# au6850_mp3.net
KiCad netlist of a schematic drawn in EAGLE
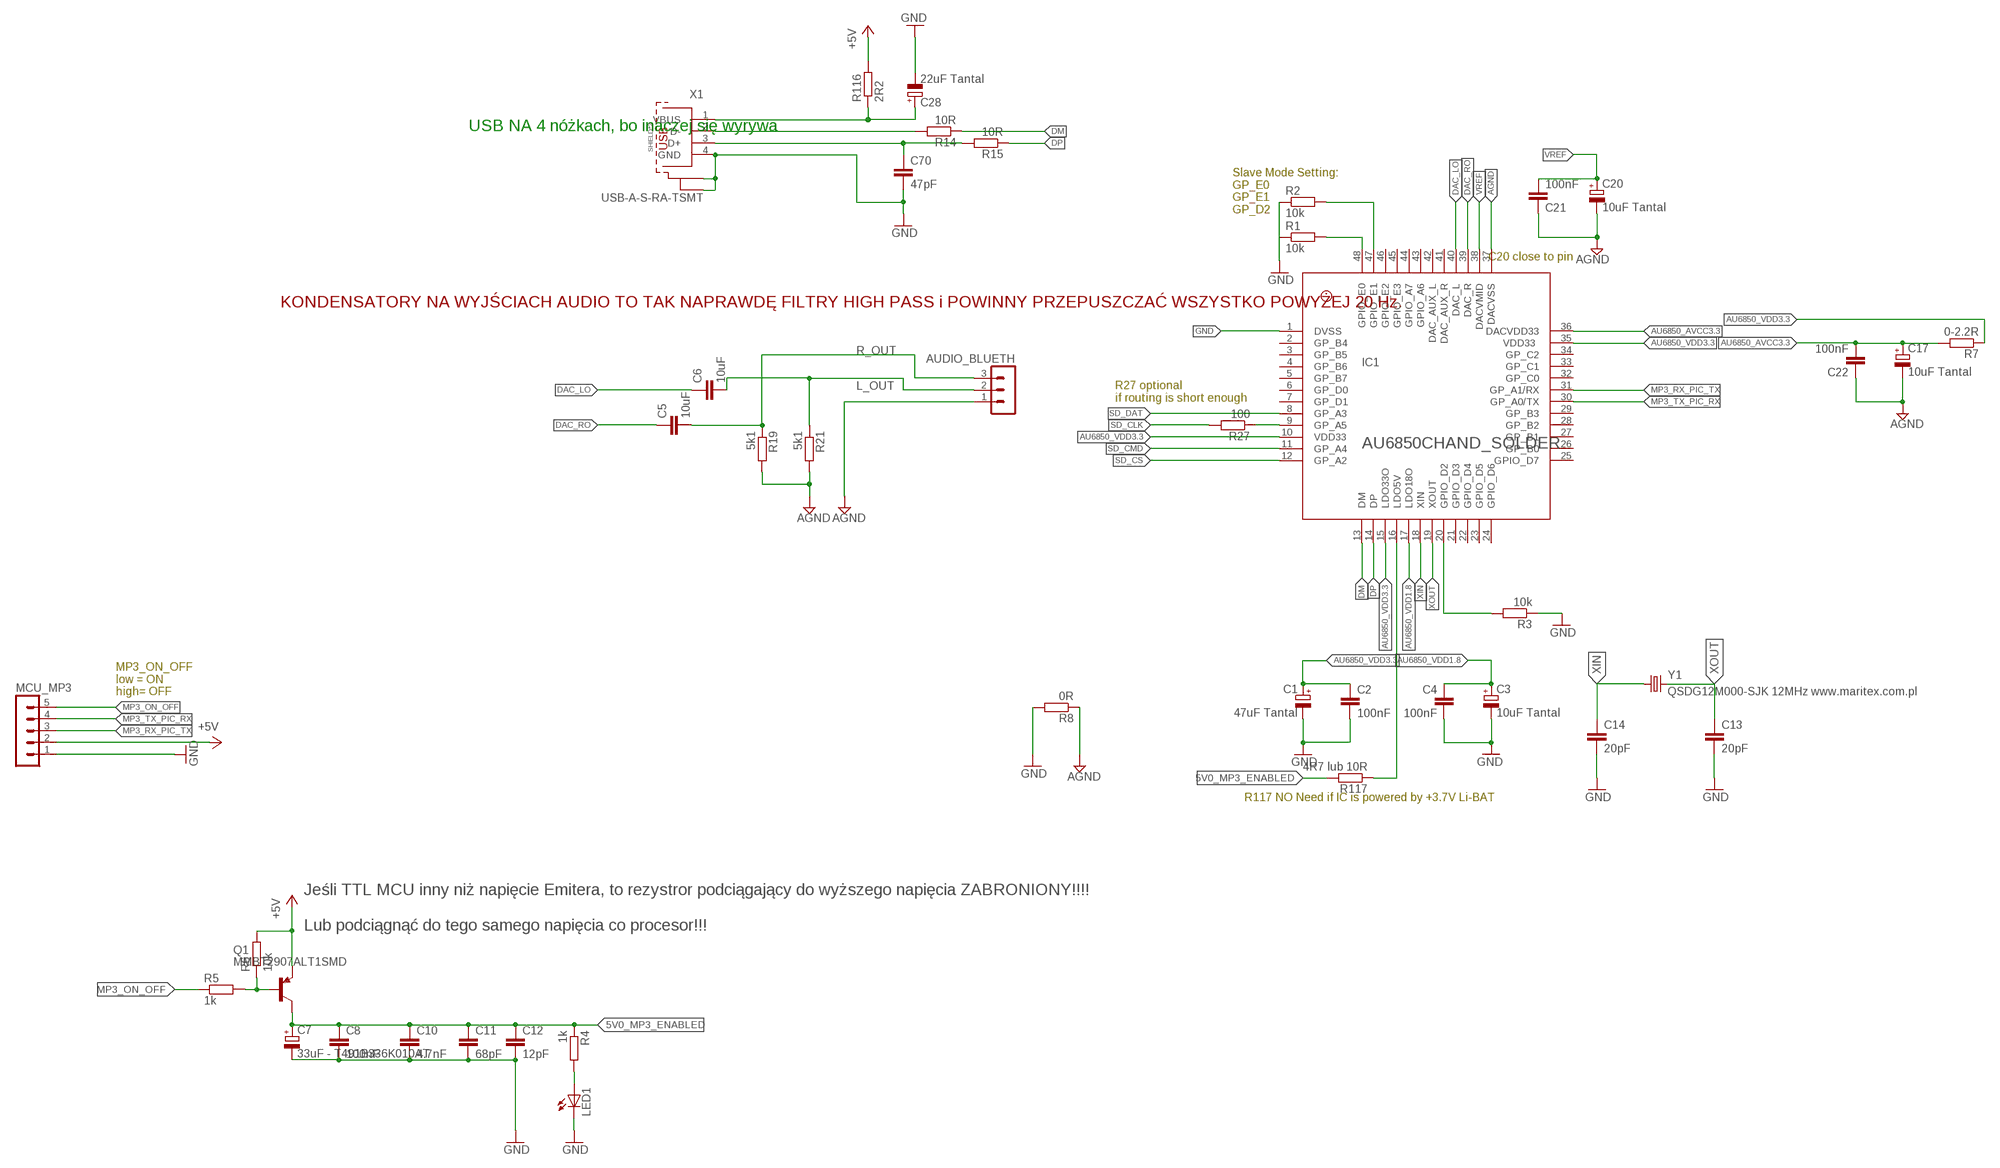
[diagram p0: schematic, sheet 1, part 1 of 2]
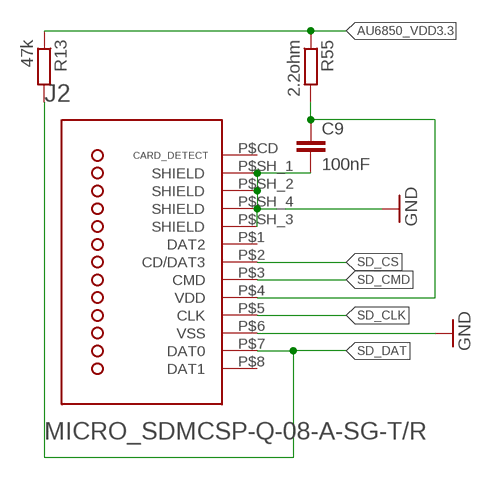
[diagram p1: schematic, sheet 1, part 2 of 2]

(export (version "E")
  (design (tool "Eeschema 10.0.6"))
  (components
    (comp (ref "AUDIO_BLUETH")
      (value "MA03-1")
      (footprint "eagle-import:MA03-1")
      (libsource (lib "eagle-import") (part "MA03-1"))
    )
    (comp (ref "C1")
      (value "47uF Tantal")
      (footprint "eagle-import:B_3528-21R")
      (fields (field (name "PARTNUM") "TAJB476K010R") (field (name "SUPPLIER") "TME"))
      (libsource (lib "eagle-import") (part "CPOL-EUB/3528-21R"))
    )
    (comp (ref "C2")
      (value "100nF")
      (footprint "eagle-import:C0805")
      (libsource (lib "eagle-import") (part "C-EUC0805"))
    )
    (comp (ref "C3")
      (value "10uF Tantal")
      (footprint "eagle-import:B_3528-21R")
      (fields (field (name "PARTNUM") "TAJA106K010R") (field (name "SUPPLIER") "TME"))
      (libsource (lib "eagle-import") (part "CPOL-EUB/3528-21R"))
    )
    (comp (ref "C4")
      (value "100nF")
      (footprint "eagle-import:C0805")
      (libsource (lib "eagle-import") (part "C-EUC0805"))
    )
    (comp (ref "C5")
      (value "10uF")
      (footprint "eagle-import:C0805")
      (libsource (lib "eagle-import") (part "C-EUC0805"))
    )
    (comp (ref "C6")
      (value "10uF")
      (footprint "eagle-import:C0805")
      (libsource (lib "eagle-import") (part "C-EUC0805"))
    )
    (comp (ref "C7")
      (value "33uF - T491B336K010AT")
      (footprint "eagle-import:SMC_B")
      (fields (field (name "PARTNUM") "TAJB336K010R") (field (name "SUPPLIER") "TME"))
      (libsource (lib "eagle-import") (part "resistor_CPOL-EUSMCB"))
    )
    (comp (ref "C8")
      (value "100nF")
      (footprint "eagle-import:C0805")
      (libsource (lib "eagle-import") (part "resistor_C-EUC0805"))
    )
    (comp (ref "C9")
      (value "100nF")
      (footprint "eagle-import:C0805")
      (libsource (lib "eagle-import") (part "resistor_C-EUC0805"))
    )
    (comp (ref "C10")
      (value "4.7nF")
      (footprint "eagle-import:C0805")
      (libsource (lib "eagle-import") (part "resistor_C-EUC0805"))
    )
    (comp (ref "C11")
      (value "68pF")
      (footprint "eagle-import:C0805")
      (libsource (lib "eagle-import") (part "resistor_C-EUC0805"))
    )
    (comp (ref "C12")
      (value "12pF")
      (footprint "eagle-import:C0603K")
      (libsource (lib "eagle-import") (part "resistor_C-EUC0603K"))
    )
    (comp (ref "C13")
      (value "20pF")
      (footprint "eagle-import:C0805")
      (libsource (lib "eagle-import") (part "resistor_C-EUC0805"))
    )
    (comp (ref "C14")
      (value "20pF")
      (footprint "eagle-import:C0805")
      (libsource (lib "eagle-import") (part "resistor_C-EUC0805"))
    )
    (comp (ref "C17")
      (value "10uF Tantal")
      (footprint "eagle-import:B_3528-21R")
      (libsource (lib "eagle-import") (part "CPOL-EUB/3528-21R"))
    )
    (comp (ref "C20")
      (value "10uF Tantal")
      (footprint "eagle-import:B_3528-21R")
      (libsource (lib "eagle-import") (part "CPOL-EUB/3528-21R"))
    )
    (comp (ref "C21")
      (value "100nF")
      (footprint "eagle-import:C0805")
      (libsource (lib "eagle-import") (part "C-EUC0805"))
    )
    (comp (ref "C22")
      (value "100nF")
      (footprint "eagle-import:C0805")
      (libsource (lib "eagle-import") (part "C-EUC0805"))
    )
    (comp (ref "C28")
      (value "22uF Tantal")
      (footprint "eagle-import:SMC_B")
      (fields (field (name "PARTNUM") "TAJB226M010R"))
      (libsource (lib "eagle-import") (part "CPOL-EUSMCB"))
    )
    (comp (ref "C70")
      (value "47pF")
      (footprint "eagle-import:C0805")
      (libsource (lib "eagle-import") (part "resistor_C-EUC0805"))
    )
    (comp (ref "IC1")
      (value "AU6850CHAND_SOLDER")
      (footprint "eagle-import:LQFP48-7X7_3MM")
      (libsource (lib "eagle-import") (part "AU6850CHAND_SOLDER"))
    )
    (comp (ref "J2")
      (value "MICRO_SDMCSP-Q-08-A-SG-T/R")
      (footprint "eagle-import:MICRO_SD_8PINS")
      (fields (field (name "PARTNUM") "MCSP-Q-08-A-SG-T/R"))
      (libsource (lib "eagle-import") (part "MICRO_SDMCSP-Q-08-A-SG-T/R"))
    )
    (comp (ref "LED1")
      (value "LED3MM")
      (footprint "eagle-import:LED3MM")
      (libsource (lib "eagle-import") (part "LED3MM"))
    )
    (comp (ref "MCU_MP3")
      (value "MA05-1")
      (footprint "eagle-import:MA05-1")
      (libsource (lib "eagle-import") (part "MA05-1"))
    )
    (comp (ref "Q1")
      (value "MMBT2907ALT1SMD")
      (footprint "eagle-import:SOT23-BEC")
      (libsource (lib "eagle-import") (part "MMBT2907SMDALT1"))
    )
    (comp (ref "R1")
      (value "10k")
      (footprint "eagle-import:R0805")
      (libsource (lib "eagle-import") (part "R-EU_R0805"))
    )
    (comp (ref "R2")
      (value "10k")
      (footprint "eagle-import:R0805")
      (libsource (lib "eagle-import") (part "R-EU_R0805"))
    )
    (comp (ref "R3")
      (value "10k")
      (footprint "eagle-import:R0805")
      (libsource (lib "eagle-import") (part "R-EU_R0805"))
    )
    (comp (ref "R4")
      (value "1k")
      (footprint "eagle-import:M0805")
      (libsource (lib "eagle-import") (part "R-EU_M0805"))
    )
    (comp (ref "R5")
      (value "1k")
      (footprint "eagle-import:M0805")
      (libsource (lib "eagle-import") (part "R-EU_M0805"))
    )
    (comp (ref "R6")
      (value "10k")
      (footprint "eagle-import:M0805")
      (libsource (lib "eagle-import") (part "R-EU_M0805"))
    )
    (comp (ref "R7")
      (value "0-2.2R")
      (footprint "eagle-import:R0805")
      (libsource (lib "eagle-import") (part "R-EU_R0805"))
    )
    (comp (ref "R8")
      (value "0R")
      (footprint "eagle-import:R0805")
      (libsource (lib "eagle-import") (part "R-EU_R0805"))
    )
    (comp (ref "R13")
      (value "47k")
      (footprint "eagle-import:R0805")
      (libsource (lib "eagle-import") (part "R-EU_R0805"))
    )
    (comp (ref "R14")
      (value "10R")
      (footprint "eagle-import:R0805")
      (libsource (lib "eagle-import") (part "R-EU_R0805"))
    )
    (comp (ref "R15")
      (value "10R")
      (footprint "eagle-import:R0805")
      (libsource (lib "eagle-import") (part "R-EU_R0805"))
    )
    (comp (ref "R19")
      (value "5k1")
      (footprint "eagle-import:R0805")
      (libsource (lib "eagle-import") (part "R-EU_R0805"))
    )
    (comp (ref "R21")
      (value "5k1")
      (footprint "eagle-import:R0805")
      (libsource (lib "eagle-import") (part "R-EU_R0805"))
    )
    (comp (ref "R27")
      (value "100")
      (footprint "eagle-import:R0805")
      (libsource (lib "eagle-import") (part "R-EU_R0805"))
    )
    (comp (ref "R55")
      (value "2.2ohm")
      (footprint "eagle-import:R0805")
      (libsource (lib "eagle-import") (part "R-EU_R0805"))
    )
    (comp (ref "R116")
      (value "2R2")
      (footprint "eagle-import:R0805")
      (libsource (lib "eagle-import") (part "R-EU_R0805"))
    )
    (comp (ref "R117")
      (value "4R7 lub 10R")
      (footprint "eagle-import:R0805")
      (libsource (lib "eagle-import") (part "R-EU_R0805"))
    )
    (comp (ref "X1")
      (value "USB-A-S-RA-TSMT")
      (footprint "eagle-import:USB-A-S-RA-TSMT")
      (libsource (lib "eagle-import") (part "USB-A-S-RA-TSMT"))
    )
    (comp (ref "Y1")
      (value "QSDG12M000-SJK 12MHz www.maritex.com.pl")
      (footprint "eagle-import:HC49UP")
      (fields (field (name "PARTNUM") "12.00M-SMDHC49S"))
      (libsource (lib "eagle-import") (part "CRYSTALSMD"))
    )
  )
  (nets
    (net (code "1") (name "+5V") (class "Default")
      (node (ref "MCU_MP3") (pin "2") (pinfunction "2_2") (pintype "passive"))
      (node (ref "Q1") (pin "E") (pinfunction "E_E") (pintype "passive"))
      (node (ref "R116") (pin "2") (pinfunction "2_2") (pintype "passive"))
      (node (ref "R6") (pin "2") (pinfunction "2_2") (pintype "passive"))
    )
    (net (code "2") (name "/L_OUT") (class "Default")
      (node (ref "AUDIO_BLUETH") (pin "2") (pinfunction "2_2") (pintype "passive"))
      (node (ref "C6") (pin "2") (pinfunction "2_2") (pintype "passive"))
      (node (ref "R21") (pin "1") (pinfunction "1_1") (pintype "passive"))
    )
    (net (code "3") (name "/R_OUT") (class "Default")
      (node (ref "AUDIO_BLUETH") (pin "3") (pinfunction "3_3") (pintype "passive"))
      (node (ref "C5") (pin "2") (pinfunction "2_2") (pintype "passive"))
      (node (ref "R19") (pin "1") (pinfunction "1_1") (pintype "passive"))
    )
    (net (code "4") (name "5V0_MP3_ENABLED") (class "Default")
      (node (ref "C10") (pin "1") (pinfunction "1_1") (pintype "passive"))
      (node (ref "C11") (pin "1") (pinfunction "1_1") (pintype "passive"))
      (node (ref "C12") (pin "1") (pinfunction "1_1") (pintype "passive"))
      (node (ref "C7") (pin "+") (pinfunction "+_+") (pintype "passive"))
      (node (ref "C8") (pin "1") (pinfunction "1_1") (pintype "passive"))
      (node (ref "Q1") (pin "C") (pinfunction "C_C") (pintype "passive"))
      (node (ref "R117") (pin "2") (pinfunction "2_2") (pintype "passive"))
      (node (ref "R4") (pin "1") (pinfunction "1_1") (pintype "passive"))
    )
    (net (code "5") (name "AGND") (class "Default")
      (node (ref "AUDIO_BLUETH") (pin "1") (pinfunction "1_1") (pintype "passive"))
      (node (ref "C17") (pin "-") (pinfunction "-_-") (pintype "passive"))
      (node (ref "C20") (pin "-") (pinfunction "-_-") (pintype "passive"))
      (node (ref "C21") (pin "1") (pinfunction "1_1") (pintype "passive"))
      (node (ref "C22") (pin "1") (pinfunction "1_1") (pintype "passive"))
      (node (ref "IC1") (pin "37") (pinfunction "DACVSS_37") (pintype "input"))
      (node (ref "R19") (pin "2") (pinfunction "2_2") (pintype "passive"))
      (node (ref "R21") (pin "2") (pinfunction "2_2") (pintype "passive"))
      (node (ref "R8") (pin "1") (pinfunction "1_1") (pintype "passive"))
    )
    (net (code "6") (name "AU6850_AVCC3.3") (class "Default")
      (node (ref "C17") (pin "+") (pinfunction "+_+") (pintype "passive"))
      (node (ref "C22") (pin "2") (pinfunction "2_2") (pintype "passive"))
      (node (ref "IC1") (pin "36") (pinfunction "DACVDD33_36") (pintype "input"))
      (node (ref "R7") (pin "2") (pinfunction "2_2") (pintype "passive"))
    )
    (net (code "7") (name "AU6850_VDD1.8") (class "Default")
      (node (ref "C3") (pin "+") (pinfunction "+_+") (pintype "passive"))
      (node (ref "C4") (pin "1") (pinfunction "1_1") (pintype "passive"))
      (node (ref "IC1") (pin "17") (pinfunction "LDO18O_17") (pintype "bidirectional"))
    )
    (net (code "8") (name "AU6850_VDD3.3") (class "Default")
      (node (ref "C1") (pin "+") (pinfunction "+_+") (pintype "passive"))
      (node (ref "C2") (pin "1") (pinfunction "1_1") (pintype "passive"))
      (node (ref "IC1") (pin "10") (pinfunction "VDD33_10") (pintype "power_in"))
      (node (ref "IC1") (pin "15") (pinfunction "LDO33O_15") (pintype "output"))
      (node (ref "IC1") (pin "35") (pinfunction "VDD33_35") (pintype "input"))
      (node (ref "R13") (pin "1") (pinfunction "1_1") (pintype "passive"))
      (node (ref "R55") (pin "1") (pinfunction "1_1") (pintype "passive"))
      (node (ref "R7") (pin "1") (pinfunction "1_1") (pintype "passive"))
    )
    (net (code "9") (name "DAC_LO") (class "Default")
      (node (ref "C6") (pin "1") (pinfunction "1_1") (pintype "passive"))
      (node (ref "IC1") (pin "40") (pinfunction "DAC_L_40") (pintype "output"))
    )
    (net (code "10") (name "DAC_RO") (class "Default")
      (node (ref "C5") (pin "1") (pinfunction "1_1") (pintype "passive"))
      (node (ref "IC1") (pin "39") (pinfunction "DAC_R_39") (pintype "output"))
    )
    (net (code "11") (name "DM") (class "Default")
      (node (ref "IC1") (pin "13") (pinfunction "DM_13") (pintype "bidirectional"))
      (node (ref "R14") (pin "1") (pinfunction "1_1") (pintype "passive"))
    )
    (net (code "12") (name "DP") (class "Default")
      (node (ref "IC1") (pin "14") (pinfunction "DP_14") (pintype "bidirectional"))
      (node (ref "R15") (pin "1") (pinfunction "1_1") (pintype "passive"))
    )
    (net (code "13") (name "GND") (class "Default")
      (node (ref "C1") (pin "-") (pinfunction "-_-") (pintype "passive"))
      (node (ref "C10") (pin "2") (pinfunction "2_2") (pintype "passive"))
      (node (ref "C11") (pin "2") (pinfunction "2_2") (pintype "passive"))
      (node (ref "C12") (pin "2") (pinfunction "2_2") (pintype "passive"))
      (node (ref "C13") (pin "2") (pinfunction "2_2") (pintype "passive"))
      (node (ref "C14") (pin "2") (pinfunction "2_2") (pintype "passive"))
      (node (ref "C2") (pin "2") (pinfunction "2_2") (pintype "passive"))
      (node (ref "C28") (pin "-") (pinfunction "-_-") (pintype "passive"))
      (node (ref "C3") (pin "-") (pinfunction "-_-") (pintype "passive"))
      (node (ref "C4") (pin "2") (pinfunction "2_2") (pintype "passive"))
      (node (ref "C7") (pin "-") (pinfunction "-_-") (pintype "passive"))
      (node (ref "C70") (pin "2") (pinfunction "2_2") (pintype "passive"))
      (node (ref "C8") (pin "2") (pinfunction "2_2") (pintype "passive"))
      (node (ref "C9") (pin "2") (pinfunction "2_2") (pintype "passive"))
      (node (ref "IC1") (pin "1") (pinfunction "DVSS_1") (pintype "bidirectional"))
      (node (ref "J2") (pin "P$6") (pinfunction "VSS_P$6") (pintype "bidirectional"))
      (node (ref "J2") (pin "P$SH_1") (pinfunction "1_GND_PAD_P$SH_1") (pintype "bidirectional"))
      (node (ref "J2") (pin "P$SH_2") (pinfunction "2_GND_PAD_P$SH_2") (pintype "bidirectional"))
      (node (ref "J2") (pin "P$SH_3") (pinfunction "3_GND_PAD_P$SH_3") (pintype "bidirectional"))
      (node (ref "J2") (pin "P$SH_4") (pinfunction "4_GND_PAD_P$SH_4") (pintype "bidirectional"))
      (node (ref "LED1") (pin "K") (pinfunction "C_K") (pintype "passive"))
      (node (ref "MCU_MP3") (pin "1") (pinfunction "1_1") (pintype "passive"))
      (node (ref "R1") (pin "1") (pinfunction "1_1") (pintype "passive"))
      (node (ref "R2") (pin "1") (pinfunction "1_1") (pintype "passive"))
      (node (ref "R3") (pin "1") (pinfunction "1_1") (pintype "passive"))
      (node (ref "R8") (pin "2") (pinfunction "2_2") (pintype "passive"))
      (node (ref "X1") (pin "4") (pinfunction "GND_4") (pintype "power_in"))
      (node (ref "X1") (pin "5") (pinfunction "SH1_5") (pintype "power_in"))
      (node (ref "X1") (pin "6") (pinfunction "SH2_6") (pintype "power_in"))
    )
    (net (code "14") (name "MP3_ON_OFF") (class "Default")
      (node (ref "MCU_MP3") (pin "5") (pinfunction "5_5") (pintype "passive"))
      (node (ref "R5") (pin "1") (pinfunction "1_1") (pintype "passive"))
    )
    (net (code "15") (name "MP3_RX_PIC_TX") (class "Default")
      (node (ref "IC1") (pin "31") (pinfunction "GP_A1/RX_31") (pintype "bidirectional"))
      (node (ref "MCU_MP3") (pin "3") (pinfunction "3_3") (pintype "passive"))
    )
    (net (code "16") (name "MP3_TX_PIC_RX") (class "Default")
      (node (ref "IC1") (pin "30") (pinfunction "GP_A0/TX_30") (pintype "bidirectional"))
      (node (ref "MCU_MP3") (pin "4") (pinfunction "4_4") (pintype "passive"))
    )
    (net (code "17") (name "Net-(IC1-GPIO_D2)") (class "Default")
      (node (ref "IC1") (pin "20") (pinfunction "GPIO_D2_20") (pintype "bidirectional"))
      (node (ref "R3") (pin "2") (pinfunction "2_2") (pintype "passive"))
    )
    (net (code "18") (name "Net-(IC1-GPIO_E0)") (class "Default")
      (node (ref "IC1") (pin "48") (pinfunction "GPIO_E0_48") (pintype "bidirectional"))
      (node (ref "R1") (pin "2") (pinfunction "2_2") (pintype "passive"))
    )
    (net (code "19") (name "Net-(IC1-GPIO_E1)") (class "Default")
      (node (ref "IC1") (pin "47") (pinfunction "GPIO_E1_47") (pintype "bidirectional"))
      (node (ref "R2") (pin "2") (pinfunction "2_2") (pintype "passive"))
    )
    (net (code "20") (name "Net-(IC1-GP_A5)") (class "Default")
      (node (ref "IC1") (pin "9") (pinfunction "GP_A5_9") (pintype "bidirectional"))
      (node (ref "R27") (pin "1") (pinfunction "1_1") (pintype "passive"))
    )
    (net (code "21") (name "Net-(IC1-LDO5V)") (class "Default")
      (node (ref "IC1") (pin "16") (pinfunction "LDO5V_16") (pintype "bidirectional"))
      (node (ref "R117") (pin "1") (pinfunction "1_1") (pintype "passive"))
    )
    (net (code "22") (name "Net-(J2-VDD)") (class "Default")
      (node (ref "C9") (pin "1") (pinfunction "1_1") (pintype "passive"))
      (node (ref "J2") (pin "P$4") (pinfunction "VDD_P$4") (pintype "bidirectional"))
      (node (ref "R55") (pin "2") (pinfunction "2_2") (pintype "passive"))
    )
    (net (code "23") (name "Net-(LED1-PadA)") (class "Default")
      (node (ref "LED1") (pin "A") (pinfunction "A_A") (pintype "passive"))
      (node (ref "R4") (pin "2") (pinfunction "2_2") (pintype "passive"))
    )
    (net (code "24") (name "Net-(Q1-PadB)") (class "Default")
      (node (ref "Q1") (pin "B") (pinfunction "B_B") (pintype "passive"))
      (node (ref "R5") (pin "2") (pinfunction "2_2") (pintype "passive"))
      (node (ref "R6") (pin "1") (pinfunction "1_1") (pintype "passive"))
    )
    (net (code "25") (name "Net-(X1-D+)") (class "Default")
      (node (ref "C70") (pin "1") (pinfunction "1_1") (pintype "passive"))
      (node (ref "R15") (pin "2") (pinfunction "2_2") (pintype "passive"))
      (node (ref "X1") (pin "3") (pinfunction "D+_3") (pintype "bidirectional"))
    )
    (net (code "26") (name "Net-(X1-D-)") (class "Default")
      (node (ref "R14") (pin "2") (pinfunction "2_2") (pintype "passive"))
      (node (ref "X1") (pin "2") (pinfunction "D-_2") (pintype "bidirectional"))
    )
    (net (code "27") (name "Net-(X1-VBUS)") (class "Default")
      (node (ref "C28") (pin "+") (pinfunction "+_+") (pintype "passive"))
      (node (ref "R116") (pin "1") (pinfunction "1_1") (pintype "passive"))
      (node (ref "X1") (pin "1") (pinfunction "VBUS_1") (pintype "power_in"))
    )
    (net (code "28") (name "SD_CLK") (class "Default")
      (node (ref "J2") (pin "P$5") (pinfunction "CLK_P$5") (pintype "bidirectional"))
      (node (ref "R27") (pin "2") (pinfunction "2_2") (pintype "passive"))
    )
    (net (code "29") (name "SD_CMD") (class "Default")
      (node (ref "IC1") (pin "11") (pinfunction "GP_A4_11") (pintype "bidirectional"))
      (node (ref "J2") (pin "P$3") (pinfunction "CMD_P$3") (pintype "bidirectional"))
    )
    (net (code "30") (name "SD_CS") (class "Default")
      (node (ref "IC1") (pin "12") (pinfunction "GP_A2_12") (pintype "bidirectional"))
      (node (ref "J2") (pin "P$2") (pinfunction "CD/DAT3_P$2") (pintype "bidirectional"))
    )
    (net (code "31") (name "SD_DAT") (class "Default")
      (node (ref "IC1") (pin "8") (pinfunction "GP_A3_8") (pintype "bidirectional"))
      (node (ref "J2") (pin "P$7") (pinfunction "DAT0_P$7") (pintype "bidirectional"))
      (node (ref "R13") (pin "2") (pinfunction "2_2") (pintype "passive"))
    )
    (net (code "32") (name "VREF") (class "Default")
      (node (ref "C20") (pin "+") (pinfunction "+_+") (pintype "passive"))
      (node (ref "C21") (pin "2") (pinfunction "2_2") (pintype "passive"))
      (node (ref "IC1") (pin "38") (pinfunction "DACVMID_38") (pintype "input"))
    )
    (net (code "33") (name "XIN") (class "Default")
      (node (ref "C14") (pin "1") (pinfunction "1_1") (pintype "passive"))
      (node (ref "IC1") (pin "18") (pinfunction "XIN_18") (pintype "input"))
      (node (ref "Y1") (pin "1") (pinfunction "1_1") (pintype "passive"))
    )
    (net (code "34") (name "XOUT") (class "Default")
      (node (ref "C13") (pin "1") (pinfunction "1_1") (pintype "passive"))
      (node (ref "IC1") (pin "19") (pinfunction "XOUT_19") (pintype "output"))
      (node (ref "Y1") (pin "2") (pinfunction "2_2") (pintype "passive"))
    )
    (net (code "35") (name "unconnected-(IC1-DAC_AUX_L-Pad42)") (class "Default")
      (node (ref "IC1") (pin "42") (pinfunction "DAC_AUX_L_42") (pintype "input"))
    )
    (net (code "36") (name "unconnected-(IC1-DAC_AUX_R-Pad41)") (class "Default")
      (node (ref "IC1") (pin "41") (pinfunction "DAC_AUX_R_41") (pintype "input"))
    )
    (net (code "37") (name "unconnected-(IC1-GPIO_A6-Pad43)") (class "Default")
      (node (ref "IC1") (pin "43") (pinfunction "GPIO_A6_43") (pintype "bidirectional"))
    )
    (net (code "38") (name "unconnected-(IC1-GPIO_A7-Pad44)") (class "Default")
      (node (ref "IC1") (pin "44") (pinfunction "GPIO_A7_44") (pintype "bidirectional"))
    )
    (net (code "39") (name "unconnected-(IC1-GPIO_D3-Pad21)") (class "Default")
      (node (ref "IC1") (pin "21") (pinfunction "GPIO_D3_21") (pintype "bidirectional"))
    )
    (net (code "40") (name "unconnected-(IC1-GPIO_D4-Pad22)") (class "Default")
      (node (ref "IC1") (pin "22") (pinfunction "GPIO_D4_22") (pintype "bidirectional"))
    )
    (net (code "41") (name "unconnected-(IC1-GPIO_D5-Pad23)") (class "Default")
      (node (ref "IC1") (pin "23") (pinfunction "GPIO_D5_23") (pintype "bidirectional"))
    )
    (net (code "42") (name "unconnected-(IC1-GPIO_D6-Pad24)") (class "Default")
      (node (ref "IC1") (pin "24") (pinfunction "GPIO_D6_24") (pintype "bidirectional"))
    )
    (net (code "43") (name "unconnected-(IC1-GPIO_D7-Pad25)") (class "Default")
      (node (ref "IC1") (pin "25") (pinfunction "GPIO_D7_25") (pintype "bidirectional"))
    )
    (net (code "44") (name "unconnected-(IC1-GPIO_E2-Pad46)") (class "Default")
      (node (ref "IC1") (pin "46") (pinfunction "GPIO_E2_46") (pintype "bidirectional"))
    )
    (net (code "45") (name "unconnected-(IC1-GPIO_E3-Pad45)") (class "Default")
      (node (ref "IC1") (pin "45") (pinfunction "GPIO_E3_45") (pintype "bidirectional"))
    )
    (net (code "46") (name "unconnected-(IC1-GP_B0-Pad26)") (class "Default")
      (node (ref "IC1") (pin "26") (pinfunction "GP_B0_26") (pintype "bidirectional"))
    )
    (net (code "47") (name "unconnected-(IC1-GP_B1-Pad27)") (class "Default")
      (node (ref "IC1") (pin "27") (pinfunction "GP_B1_27") (pintype "bidirectional"))
    )
    (net (code "48") (name "unconnected-(IC1-GP_B2-Pad28)") (class "Default")
      (node (ref "IC1") (pin "28") (pinfunction "GP_B2_28") (pintype "bidirectional"))
    )
    (net (code "49") (name "unconnected-(IC1-GP_B3-Pad29)") (class "Default")
      (node (ref "IC1") (pin "29") (pinfunction "GP_B3_29") (pintype "bidirectional"))
    )
    (net (code "50") (name "unconnected-(IC1-GP_B4-Pad2)") (class "Default")
      (node (ref "IC1") (pin "2") (pinfunction "GP_B4_2") (pintype "bidirectional"))
    )
    (net (code "51") (name "unconnected-(IC1-GP_B5-Pad3)") (class "Default")
      (node (ref "IC1") (pin "3") (pinfunction "GP_B5_3") (pintype "bidirectional"))
    )
    (net (code "52") (name "unconnected-(IC1-GP_B6-Pad4)") (class "Default")
      (node (ref "IC1") (pin "4") (pinfunction "GP_B6_4") (pintype "bidirectional"))
    )
    (net (code "53") (name "unconnected-(IC1-GP_B7-Pad5)") (class "Default")
      (node (ref "IC1") (pin "5") (pinfunction "GP_B7_5") (pintype "bidirectional"))
    )
    (net (code "54") (name "unconnected-(IC1-GP_C0-Pad32)") (class "Default")
      (node (ref "IC1") (pin "32") (pinfunction "GP_C0_32") (pintype "bidirectional"))
    )
    (net (code "55") (name "unconnected-(IC1-GP_C1-Pad33)") (class "Default")
      (node (ref "IC1") (pin "33") (pinfunction "GP_C1_33") (pintype "bidirectional"))
    )
    (net (code "56") (name "unconnected-(IC1-GP_C2-Pad34)") (class "Default")
      (node (ref "IC1") (pin "34") (pinfunction "GP_C2_34") (pintype "bidirectional"))
    )
    (net (code "57") (name "unconnected-(IC1-GP_D0-Pad6)") (class "Default")
      (node (ref "IC1") (pin "6") (pinfunction "GP_D0_6") (pintype "bidirectional"))
    )
    (net (code "58") (name "unconnected-(IC1-GP_D1-Pad7)") (class "Default")
      (node (ref "IC1") (pin "7") (pinfunction "GP_D1_7") (pintype "bidirectional"))
    )
    (net (code "59") (name "unconnected-(J2-CARD_DETECT_SW-PadP$CD)") (class "Default")
      (node (ref "J2") (pin "P$CD") (pinfunction "CARD_DETECT_SW_P$CD") (pintype "bidirectional"))
    )
    (net (code "60") (name "unconnected-(J2-DAT1-PadP$8)") (class "Default")
      (node (ref "J2") (pin "P$8") (pinfunction "DAT1_P$8") (pintype "bidirectional"))
    )
    (net (code "61") (name "unconnected-(J2-DAT2-PadP$1)") (class "Default")
      (node (ref "J2") (pin "P$1") (pinfunction "DAT2_P$1") (pintype "bidirectional"))
    )
  )
)
